# ESP_12F_CLOCK_MAXTRIX.net
KiCad netlist of a schematic drawn in Altium Designer
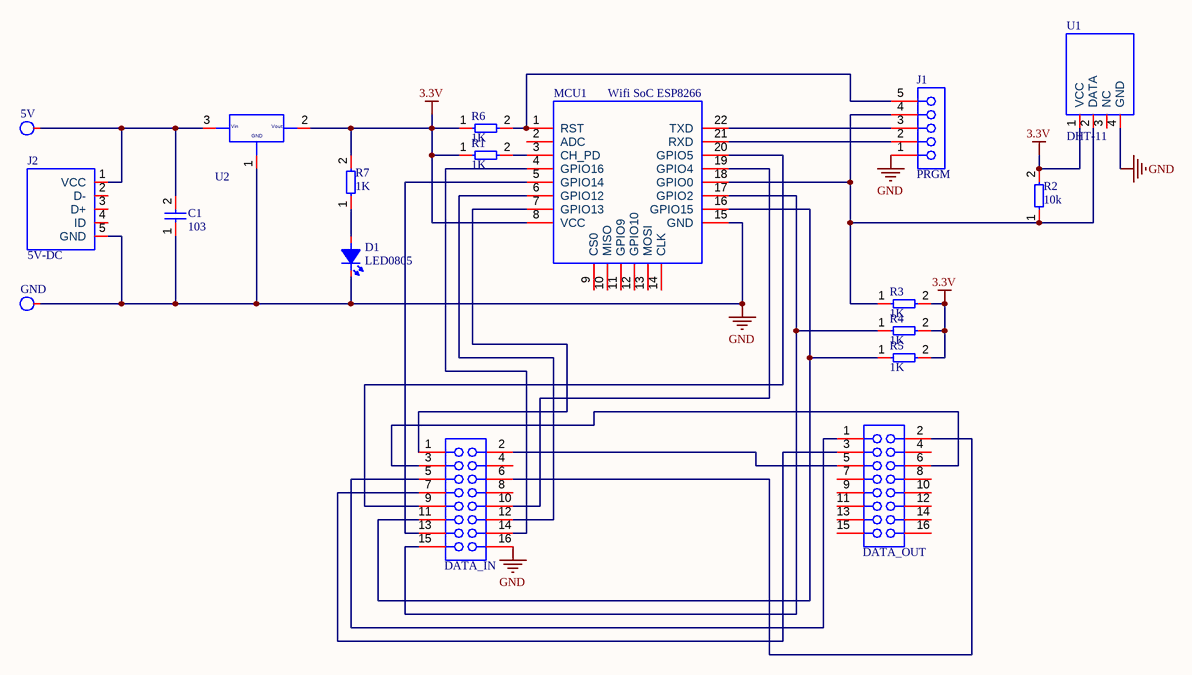
[diagram p0: ESP_12F_CLOCK_MAXTRIX.SchDoc]

(export (version "E")
  (design (tool "Eeschema 10.0.6"))
  (components
    (comp (ref "5V")
      (value "SolderPoint")
      (footprint "SolderPoint")
      (libsource (lib "Lib31082020") (part "SolderPoint"))
    )
    (comp (ref "C1") (value "103") (footprint "C0805") (libsource (lib "Lib31082020") (part "C0805")))
    (comp (ref "D1")
      (value "LED0805")
      (footprint "L0805RED")
      (libsource (lib "Lib31082020") (part "LED0805"))
    )
    (comp (ref "DATA_IN")
      (value "DATA_IN")
      (footprint "Header 8x2 TH Pitch 2.54mm")
      (libsource (lib "Lib31082020") (part "Header 8x2 TH Pitch 2.54mm"))
    )
    (comp (ref "DATA_OUT")
      (value "DATA_OUT")
      (footprint "Header 8x2 TH Pitch 2.54mm")
      (libsource (lib "Lib31082020") (part "Header 8x2 TH Pitch 2.54mm"))
    )
    (comp (ref "GND")
      (value "SolderPoint")
      (footprint "SolderPoint")
      (libsource (lib "Lib31082020") (part "SolderPoint"))
    )
    (comp (ref "J1")
      (value "PRGM")
      (footprint "Header 5x1 TH Pitch 2.54mm")
      (libsource (lib "Lib31082020") (part "Header 5x1 TH Pitch 2.54mm"))
    )
    (comp (ref "J2")
      (value "5V-DC")
      (footprint "Micro USB 01")
      (libsource (lib "Lib31082020") (part "Micro USB (AB 2.0)"))
    )
    (comp (ref "MCU1")
      (value "Wifi SoC ESP8266")
      (footprint "ESP-12F")
      (libsource (lib "Lib31082020") (part "ESP-12F"))
    )
    (comp (ref "R1") (value "1K") (footprint "R0805") (libsource (lib "Lib31082020") (part "Resistor SMD")))
    (comp (ref "R2") (value "10k") (footprint "R0805") (libsource (lib "") (part "Resistor SMD_1")))
    (comp (ref "R3") (value "1K") (footprint "R0805") (libsource (lib "Lib31082020") (part "Resistor SMD")))
    (comp (ref "R4") (value "1K") (footprint "R0805") (libsource (lib "Lib31082020") (part "Resistor SMD")))
    (comp (ref "R5") (value "1K") (footprint "R0805") (libsource (lib "Lib31082020") (part "Resistor SMD")))
    (comp (ref "R6") (value "1K") (footprint "R0805") (libsource (lib "Lib31082020") (part "Resistor SMD")))
    (comp (ref "R7") (value "1K") (footprint "R0805") (libsource (lib "") (part "Resistor SMD_1")))
    (comp (ref "U1") (value "DHT-11") (footprint "DHT-11") (libsource (lib "Lib31082020") (part "DHT-11")))
    (comp (ref "U2")
      (value "AMS1117")
      (footprint "SOT223-3")
      (libsource (lib "Lib31082020") (part "AMS1117(SOT-223)"))
    )
  )
  (nets
    (net (code "1") (name "3.3V") (class "Default")
      (node (ref "MCU1") (pin "8") (pinfunction "VCC_8") (pintype "passive"))
      (node (ref "R1") (pin "1") (pinfunction "1_1") (pintype "passive"))
      (node (ref "R2") (pin "2") (pinfunction "2_2") (pintype "passive"))
      (node (ref "R3") (pin "2") (pinfunction "2_2") (pintype "passive"))
      (node (ref "R4") (pin "2") (pinfunction "2_2") (pintype "passive"))
      (node (ref "R5") (pin "2") (pinfunction "2_2") (pintype "passive"))
      (node (ref "R6") (pin "1") (pinfunction "1_1") (pintype "passive"))
      (node (ref "R7") (pin "2") (pinfunction "2_2") (pintype "passive"))
      (node (ref "U1") (pin "1") (pinfunction "VCC_1") (pintype "passive"))
      (node (ref "U2") (pin "2") (pinfunction "2_2") (pintype "passive"))
    )
    (net (code "2") (name "GND") (class "Default")
      (node (ref "C1") (pin "1") (pinfunction "1_1") (pintype "passive"))
      (node (ref "D1") (pin "2") (pinfunction "K_2") (pintype "passive"))
      (node (ref "DATA_IN") (pin "16") (pinfunction "16_16") (pintype "passive"))
      (node (ref "GND") (pin "1") (pinfunction "1_1") (pintype "passive"))
      (node (ref "J1") (pin "1") (pinfunction "1_1") (pintype "passive"))
      (node (ref "J2") (pin "5") (pinfunction "GND_5") (pintype "passive"))
      (node (ref "MCU1") (pin "15") (pinfunction "GND_15") (pintype "passive"))
      (node (ref "U1") (pin "4") (pinfunction "GND_4") (pintype "passive"))
      (node (ref "U2") (pin "1") (pinfunction "1_1") (pintype "passive"))
    )
    (net (code "3") (name "Net-(D1-A)") (class "Default")
      (node (ref "D1") (pin "1") (pinfunction "A_1") (pintype "passive"))
      (node (ref "R7") (pin "1") (pinfunction "1_1") (pintype "passive"))
    )
    (net (code "4") (name "Net-(DATA_IN-Pad2)") (class "Default")
      (node (ref "DATA_IN") (pin "2") (pinfunction "2_2") (pintype "passive"))
      (node (ref "DATA_OUT") (pin "5") (pinfunction "5_5") (pintype "passive"))
    )
    (net (code "5") (name "Net-(DATA_IN-Pad3)") (class "Default")
      (node (ref "DATA_IN") (pin "3") (pinfunction "3_3") (pintype "passive"))
      (node (ref "DATA_OUT") (pin "6") (pinfunction "6_6") (pintype "passive"))
    )
    (net (code "6") (name "Net-(DATA_IN-Pad5)") (class "Default")
      (node (ref "DATA_IN") (pin "5") (pinfunction "5_5") (pintype "passive"))
      (node (ref "DATA_OUT") (pin "1") (pinfunction "1_1") (pintype "passive"))
    )
    (net (code "7") (name "Net-(DATA_IN-Pad6)") (class "Default")
      (node (ref "DATA_IN") (pin "6") (pinfunction "6_6") (pintype "passive"))
      (node (ref "DATA_OUT") (pin "2") (pinfunction "2_2") (pintype "passive"))
    )
    (net (code "8") (name "Net-(DATA_IN-Pad7)") (class "Default")
      (node (ref "DATA_IN") (pin "7") (pinfunction "7_7") (pintype "passive"))
      (node (ref "DATA_OUT") (pin "3") (pinfunction "3_3") (pintype "passive"))
    )
    (net (code "9") (name "Net-(J2-VCC)") (class "Default")
      (node (ref "5V") (pin "1") (pinfunction "1_1") (pintype "passive"))
      (node (ref "C1") (pin "2") (pinfunction "2_2") (pintype "passive"))
      (node (ref "J2") (pin "1") (pinfunction "VCC_1") (pintype "passive"))
      (node (ref "U2") (pin "3") (pinfunction "3_3") (pintype "passive"))
    )
    (net (code "10") (name "Net-(MCU1-CH_PD)") (class "Default")
      (node (ref "MCU1") (pin "3") (pinfunction "CH_PD_3") (pintype "passive"))
      (node (ref "R1") (pin "2") (pinfunction "2_2") (pintype "passive"))
    )
    (net (code "11") (name "Net-(MCU1-GPIO0)") (class "Default")
      (node (ref "J1") (pin "4") (pinfunction "4_4") (pintype "passive"))
      (node (ref "MCU1") (pin "18") (pinfunction "GPIO0_18") (pintype "passive"))
      (node (ref "R2") (pin "1") (pinfunction "1_1") (pintype "passive"))
      (node (ref "R3") (pin "1") (pinfunction "1_1") (pintype "passive"))
      (node (ref "U1") (pin "2") (pinfunction "DATA_2") (pintype "passive"))
    )
    (net (code "12") (name "Net-(MCU1-GPIO2)") (class "Default")
      (node (ref "DATA_IN") (pin "15") (pinfunction "15_15") (pintype "passive"))
      (node (ref "MCU1") (pin "17") (pinfunction "GPIO2_17") (pintype "passive"))
      (node (ref "R4") (pin "1") (pinfunction "1_1") (pintype "passive"))
    )
    (net (code "13") (name "Net-(MCU1-GPIO4)") (class "Default")
      (node (ref "DATA_IN") (pin "10") (pinfunction "10_10") (pintype "passive"))
      (node (ref "MCU1") (pin "19") (pinfunction "GPIO4_19") (pintype "passive"))
    )
    (net (code "14") (name "Net-(MCU1-GPIO5)") (class "Default")
      (node (ref "DATA_IN") (pin "9") (pinfunction "9_9") (pintype "passive"))
      (node (ref "MCU1") (pin "20") (pinfunction "GPIO5_20") (pintype "passive"))
    )
    (net (code "15") (name "Net-(MCU1-GPIO12)") (class "Default")
      (node (ref "DATA_IN") (pin "12") (pinfunction "12_12") (pintype "passive"))
      (node (ref "MCU1") (pin "6") (pinfunction "GPIO12_6") (pintype "passive"))
    )
    (net (code "16") (name "Net-(MCU1-GPIO13)") (class "Default")
      (node (ref "DATA_IN") (pin "1") (pinfunction "1_1") (pintype "passive"))
      (node (ref "MCU1") (pin "7") (pinfunction "GPIO13_7") (pintype "passive"))
    )
    (net (code "17") (name "Net-(MCU1-GPIO14)") (class "Default")
      (node (ref "DATA_IN") (pin "13") (pinfunction "13_13") (pintype "passive"))
      (node (ref "MCU1") (pin "5") (pinfunction "GPIO14_5") (pintype "passive"))
    )
    (net (code "18") (name "Net-(MCU1-GPIO15)") (class "Default")
      (node (ref "DATA_IN") (pin "11") (pinfunction "11_11") (pintype "passive"))
      (node (ref "MCU1") (pin "16") (pinfunction "GPIO15_16") (pintype "passive"))
      (node (ref "R5") (pin "1") (pinfunction "1_1") (pintype "passive"))
    )
    (net (code "19") (name "Net-(MCU1-GPIO16)") (class "Default")
      (node (ref "DATA_IN") (pin "14") (pinfunction "14_14") (pintype "passive"))
      (node (ref "MCU1") (pin "4") (pinfunction "GPIO16_4") (pintype "passive"))
    )
    (net (code "20") (name "Net-(MCU1-RST)") (class "Default")
      (node (ref "J1") (pin "5") (pinfunction "5_5") (pintype "passive"))
      (node (ref "MCU1") (pin "1") (pinfunction "RST_1") (pintype "passive"))
      (node (ref "R6") (pin "2") (pinfunction "2_2") (pintype "passive"))
    )
    (net (code "21") (name "Net-(MCU1-RXD)") (class "Default")
      (node (ref "J1") (pin "2") (pinfunction "2_2") (pintype "passive"))
      (node (ref "MCU1") (pin "21") (pinfunction "RXD_21") (pintype "passive"))
    )
    (net (code "22") (name "Net-(MCU1-TXD)") (class "Default")
      (node (ref "J1") (pin "3") (pinfunction "3_3") (pintype "passive"))
      (node (ref "MCU1") (pin "22") (pinfunction "TXD_22") (pintype "passive"))
    )
    (net (code "23") (name "unconnected-(DATA_IN-Pad4)") (class "Default")
      (node (ref "DATA_IN") (pin "4") (pinfunction "4_4") (pintype "passive"))
    )
    (net (code "24") (name "unconnected-(DATA_IN-Pad8)") (class "Default")
      (node (ref "DATA_IN") (pin "8") (pinfunction "8_8") (pintype "passive"))
    )
    (net (code "25") (name "unconnected-(DATA_OUT-Pad4)") (class "Default")
      (node (ref "DATA_OUT") (pin "4") (pinfunction "4_4") (pintype "passive"))
    )
    (net (code "26") (name "unconnected-(DATA_OUT-Pad7)") (class "Default")
      (node (ref "DATA_OUT") (pin "7") (pinfunction "7_7") (pintype "passive"))
    )
    (net (code "27") (name "unconnected-(DATA_OUT-Pad8)") (class "Default")
      (node (ref "DATA_OUT") (pin "8") (pinfunction "8_8") (pintype "passive"))
    )
    (net (code "28") (name "unconnected-(DATA_OUT-Pad9)") (class "Default")
      (node (ref "DATA_OUT") (pin "9") (pinfunction "9_9") (pintype "passive"))
    )
    (net (code "29") (name "unconnected-(DATA_OUT-Pad10)") (class "Default")
      (node (ref "DATA_OUT") (pin "10") (pinfunction "10_10") (pintype "passive"))
    )
    (net (code "30") (name "unconnected-(DATA_OUT-Pad11)") (class "Default")
      (node (ref "DATA_OUT") (pin "11") (pinfunction "11_11") (pintype "passive"))
    )
    (net (code "31") (name "unconnected-(DATA_OUT-Pad12)") (class "Default")
      (node (ref "DATA_OUT") (pin "12") (pinfunction "12_12") (pintype "passive"))
    )
    (net (code "32") (name "unconnected-(DATA_OUT-Pad13)") (class "Default")
      (node (ref "DATA_OUT") (pin "13") (pinfunction "13_13") (pintype "passive"))
    )
    (net (code "33") (name "unconnected-(DATA_OUT-Pad14)") (class "Default")
      (node (ref "DATA_OUT") (pin "14") (pinfunction "14_14") (pintype "passive"))
    )
    (net (code "34") (name "unconnected-(DATA_OUT-Pad15)") (class "Default")
      (node (ref "DATA_OUT") (pin "15") (pinfunction "15_15") (pintype "passive"))
    )
    (net (code "35") (name "unconnected-(DATA_OUT-Pad16)") (class "Default")
      (node (ref "DATA_OUT") (pin "16") (pinfunction "16_16") (pintype "passive"))
    )
    (net (code "36") (name "unconnected-(J2-D+-Pad3)") (class "Default")
      (node (ref "J2") (pin "3") (pinfunction "D+_3") (pintype "passive"))
    )
    (net (code "37") (name "unconnected-(J2-D--Pad2)") (class "Default")
      (node (ref "J2") (pin "2") (pinfunction "D-_2") (pintype "passive"))
    )
    (net (code "38") (name "unconnected-(J2-ID-Pad4)") (class "Default")
      (node (ref "J2") (pin "4") (pinfunction "ID_4") (pintype "passive"))
    )
    (net (code "39") (name "unconnected-(MCU1-ADC-Pad2)") (class "Default")
      (node (ref "MCU1") (pin "2") (pinfunction "ADC_2") (pintype "passive"))
    )
    (net (code "40") (name "unconnected-(MCU1-CLK-Pad14)") (class "Default")
      (node (ref "MCU1") (pin "14") (pinfunction "CLK_14") (pintype "passive"))
    )
    (net (code "41") (name "unconnected-(MCU1-CS0-Pad9)") (class "Default")
      (node (ref "MCU1") (pin "9") (pinfunction "CS0_9") (pintype "passive"))
    )
    (net (code "42") (name "unconnected-(MCU1-GPIO9-Pad11)") (class "Default")
      (node (ref "MCU1") (pin "11") (pinfunction "GPIO9_11") (pintype "passive"))
    )
    (net (code "43") (name "unconnected-(MCU1-GPIO10-Pad12)") (class "Default")
      (node (ref "MCU1") (pin "12") (pinfunction "GPIO10_12") (pintype "passive"))
    )
    (net (code "44") (name "unconnected-(MCU1-MISO-Pad10)") (class "Default")
      (node (ref "MCU1") (pin "10") (pinfunction "MISO_10") (pintype "passive"))
    )
    (net (code "45") (name "unconnected-(MCU1-MOSI-Pad13)") (class "Default")
      (node (ref "MCU1") (pin "13") (pinfunction "MOSI_13") (pintype "passive"))
    )
    (net (code "46") (name "unconnected-(U1-NC-Pad3)") (class "Default")
      (node (ref "U1") (pin "3") (pinfunction "NC_3") (pintype "passive"))
    )
  )
)
